# Testboard_Cables.net
KiCad netlist of a schematic drawn in EAGLE
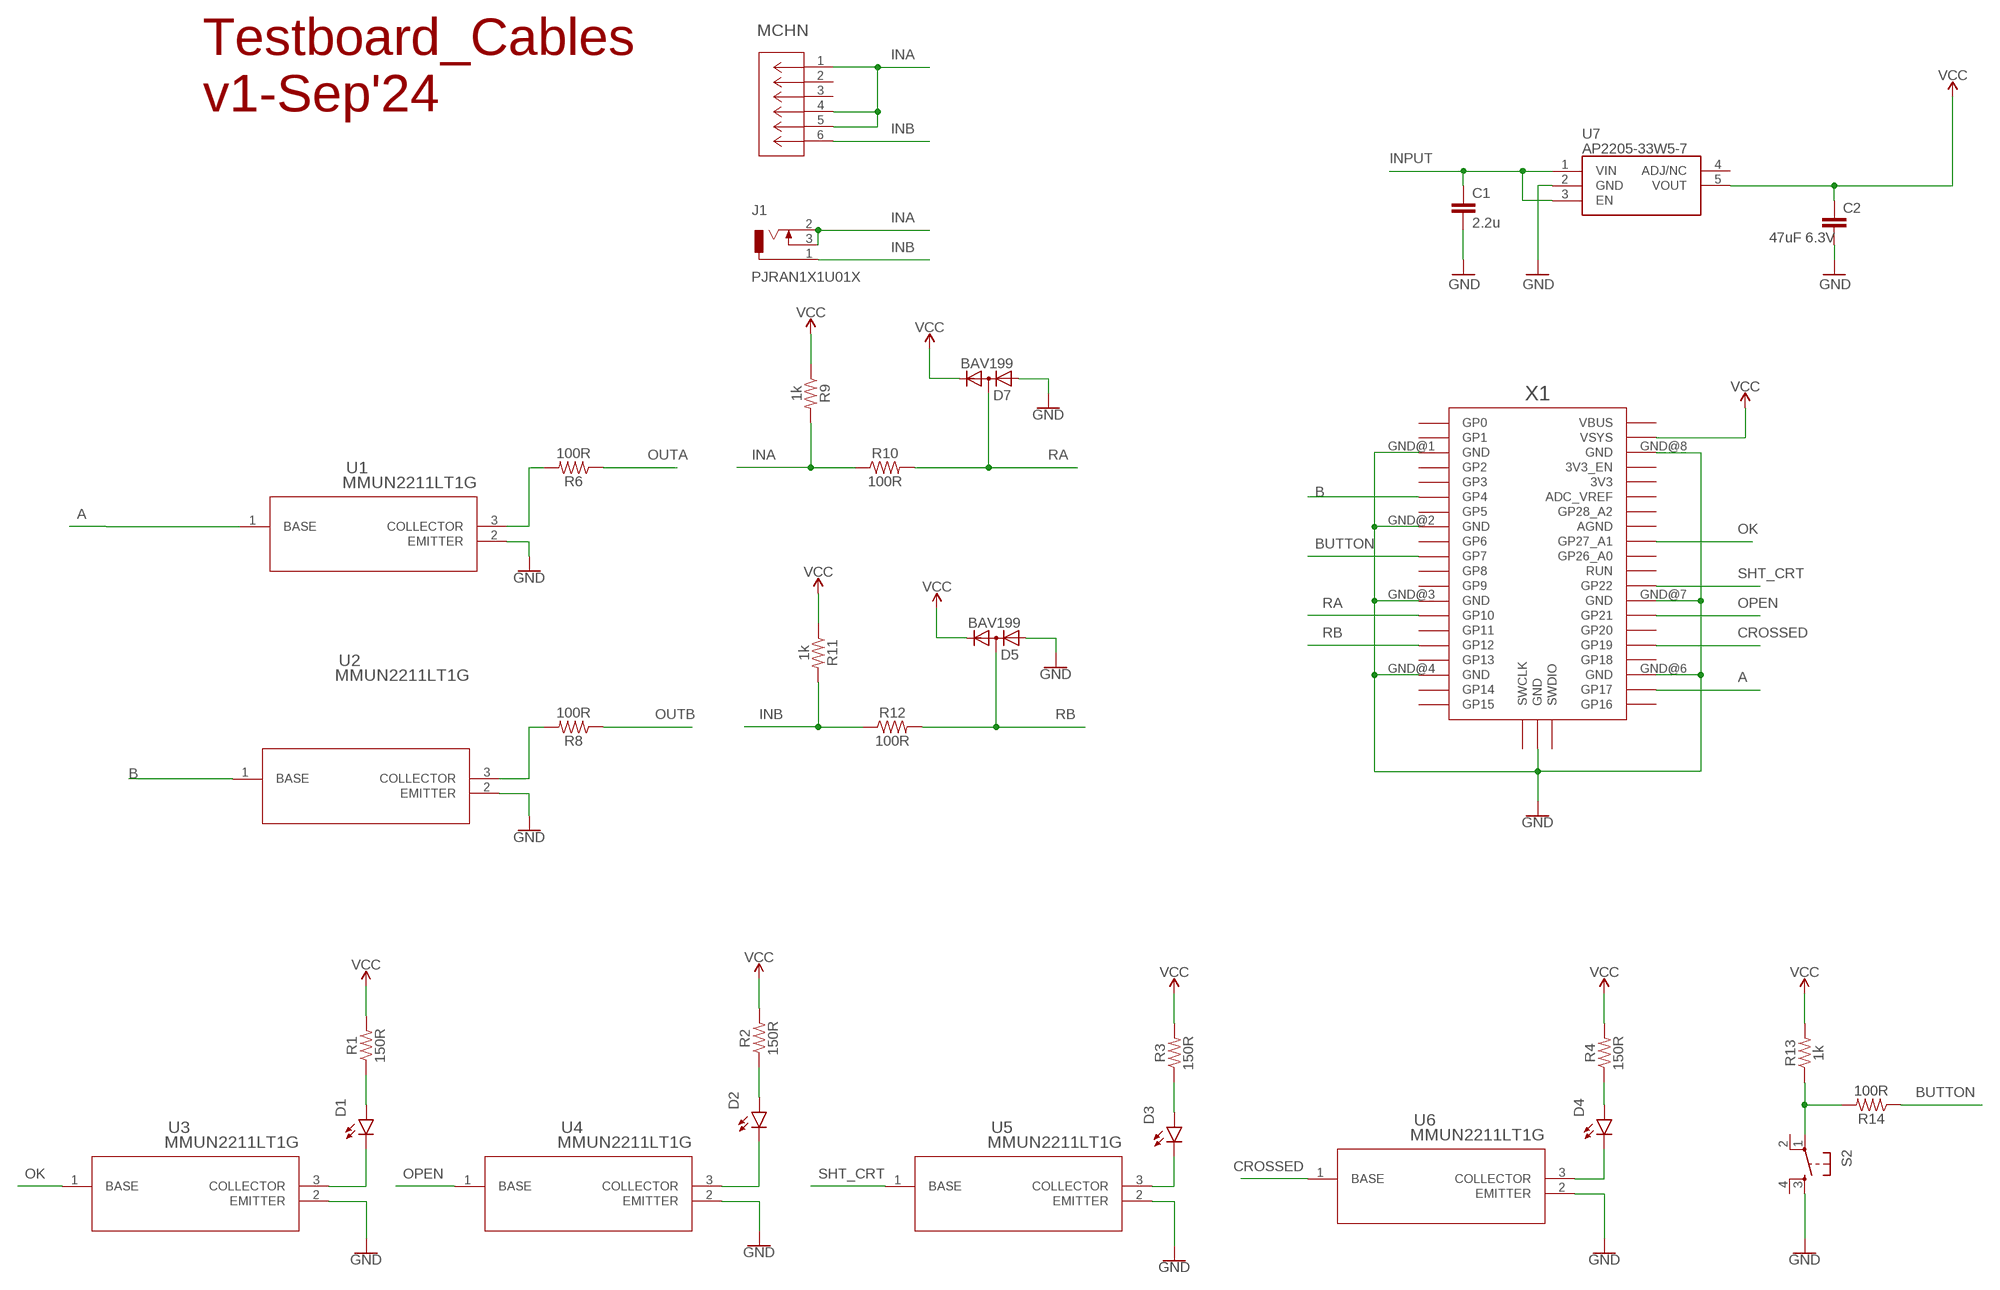
[diagram p0: schematic, sheet 1]

(export (version "E")
  (design (tool "Eeschema 10.0.6"))
  (components
    (comp (ref "C1")
      (value "2.2u")
      (footprint "eagle-import:0603-CAP")
      (libsource (lib "eagle-import") (part "4.7UF-6.3V-10%(0603)0603"))
    )
    (comp (ref "C2")
      (value "47uF 6.3V")
      (footprint "eagle-import:0603-CAP")
      (libsource (lib "eagle-import") (part "4.7UF-6.3V-10%(0603)0603"))
    )
    (comp (ref "D1")
      (value "LED3MM")
      (footprint "eagle-import:LED_3MM")
      (libsource (lib "eagle-import") (part "LED3MM"))
    )
    (comp (ref "D2")
      (value "LED3MM")
      (footprint "eagle-import:LED_3MM")
      (libsource (lib "eagle-import") (part "LED3MM"))
    )
    (comp (ref "D3")
      (value "LED3MM")
      (footprint "eagle-import:LED_3MM")
      (libsource (lib "eagle-import") (part "LED3MM"))
    )
    (comp (ref "D4")
      (value "LED3MM")
      (footprint "eagle-import:LED_3MM")
      (libsource (lib "eagle-import") (part "LED3MM"))
    )
    (comp (ref "D5")
      (value "BAV199")
      (footprint "eagle-import:SOT23")
      (libsource (lib "eagle-import") (part "BAV199"))
    )
    (comp (ref "D7")
      (value "BAV199")
      (footprint "eagle-import:SOT23")
      (libsource (lib "eagle-import") (part "BAV199"))
    )
    (comp (ref "J1")
      (value "PJRAN1X1U01X")
      (footprint "eagle-import:PJRAN1X1U01X")
      (fields
        (field (name "DIGIKEY_PART_NUMBER") "PJRAN1X1U01X-ND")
        (field (name "MANUFACTURER") "Switchcraft Inc.")
        (field (name "CREATED_BY") "PCBLayout.com")
      )
      (libsource (lib "eagle-import") (part "PJRAN1X1U01X"))
    )
    (comp (ref "MCHN")
      (value "ACJS-MHDR")
      (footprint "eagle-import:CONN_MHDR_AMP")
      (fields (field (name "COPYRIGHT") "Copyright (C) 2018 Accelerated Designs. All rights reserved"))
      (libsource (lib "eagle-import") (part "ACJS-MHDR"))
    )
    (comp (ref "R1")
      (value "150R")
      (footprint "eagle-import:1206")
      (libsource (lib "eagle-import") (part "RESISTOR1206"))
    )
    (comp (ref "R2")
      (value "150R")
      (footprint "eagle-import:1206")
      (libsource (lib "eagle-import") (part "RESISTOR1206"))
    )
    (comp (ref "R3")
      (value "150R")
      (footprint "eagle-import:1206")
      (libsource (lib "eagle-import") (part "RESISTOR1206"))
    )
    (comp (ref "R4")
      (value "150R")
      (footprint "eagle-import:1206")
      (libsource (lib "eagle-import") (part "RESISTOR1206"))
    )
    (comp (ref "R6")
      (value "100R")
      (footprint "eagle-import:1206")
      (libsource (lib "eagle-import") (part "RESISTOR1206"))
    )
    (comp (ref "R8")
      (value "100R")
      (footprint "eagle-import:1206")
      (libsource (lib "eagle-import") (part "RESISTOR1206"))
    )
    (comp (ref "R9")
      (value "1k")
      (footprint "eagle-import:1206")
      (libsource (lib "eagle-import") (part "RESISTOR1206"))
    )
    (comp (ref "R10")
      (value "100R")
      (footprint "eagle-import:1206")
      (libsource (lib "eagle-import") (part "RESISTOR1206"))
    )
    (comp (ref "R11")
      (value "1k")
      (footprint "eagle-import:1206")
      (libsource (lib "eagle-import") (part "RESISTOR1206"))
    )
    (comp (ref "R12")
      (value "100R")
      (footprint "eagle-import:1206")
      (libsource (lib "eagle-import") (part "RESISTOR1206"))
    )
    (comp (ref "R13")
      (value "1k")
      (footprint "eagle-import:1206")
      (libsource (lib "eagle-import") (part "RESISTOR1206"))
    )
    (comp (ref "R14")
      (value "100R")
      (footprint "eagle-import:1206")
      (libsource (lib "eagle-import") (part "RESISTOR1206"))
    )
    (comp (ref "S2")
      (value "TAC_SWITCH_KSC931G-SMD")
      (footprint "eagle-import:TAC_SW_SMD_KSC931G")
      (libsource (lib "eagle-import") (part "TAC_SWITCH_KSC931G-SMD"))
    )
    (comp (ref "U1")
      (value "MMUN2211LT1G")
      (footprint "eagle-import:SOT-23-3_1P4X3P040_ONS")
      (fields (field (name "COPYRIGHT") "Copyright (C) 2024 Ultra Librarian. All rights reserved."))
      (libsource (lib "eagle-import") (part "MMUN2211LT1G"))
    )
    (comp (ref "U2")
      (value "MMUN2211LT1G")
      (footprint "eagle-import:SOT-23-3_1P4X3P040_ONS")
      (fields (field (name "COPYRIGHT") "Copyright (C) 2024 Ultra Librarian. All rights reserved."))
      (libsource (lib "eagle-import") (part "MMUN2211LT1G"))
    )
    (comp (ref "U3")
      (value "MMUN2211LT1G")
      (footprint "eagle-import:SOT-23-3_1P4X3P040_ONS")
      (fields (field (name "COPYRIGHT") "Copyright (C) 2024 Ultra Librarian. All rights reserved."))
      (libsource (lib "eagle-import") (part "MMUN2211LT1G"))
    )
    (comp (ref "U4")
      (value "MMUN2211LT1G")
      (footprint "eagle-import:SOT-23-3_1P4X3P040_ONS")
      (fields (field (name "COPYRIGHT") "Copyright (C) 2024 Ultra Librarian. All rights reserved."))
      (libsource (lib "eagle-import") (part "MMUN2211LT1G"))
    )
    (comp (ref "U5")
      (value "MMUN2211LT1G")
      (footprint "eagle-import:SOT-23-3_1P4X3P040_ONS")
      (fields (field (name "COPYRIGHT") "Copyright (C) 2024 Ultra Librarian. All rights reserved."))
      (libsource (lib "eagle-import") (part "MMUN2211LT1G"))
    )
    (comp (ref "U6")
      (value "MMUN2211LT1G")
      (footprint "eagle-import:SOT-23-3_1P4X3P040_ONS")
      (fields (field (name "COPYRIGHT") "Copyright (C) 2024 Ultra Librarian. All rights reserved."))
      (libsource (lib "eagle-import") (part "MMUN2211LT1G"))
    )
    (comp (ref "U7")
      (value "AP2205-33W5-7")
      (footprint "eagle-import:SOT95P282X145-5N")
      (fields
        (field (name "MANUFACTURER_PART_NUMBER") "AP2205-W5-7")
        (field (name "MOUSER_PART_NUMBER") "621-AP2205-W5-7")
      )
      (libsource (lib "eagle-import") (part "AP2205-W5-7"))
    )
    (comp (ref "X1")
      (value "RPI_PICO_IG-TH")
      (footprint "eagle-import:RPI_PICO_TH")
      (libsource (lib "eagle-import") (part "RPI_PICO_IG-TH"))
    )
  )
  (nets
    (net (code "1") (name "/A") (class "Default")
      (node (ref "U1") (pin "1") (pinfunction "BASE_1") (pintype "passive"))
      (node (ref "X1") (pin "GP17") (pinfunction "GP17_GP17") (pintype "bidirectional"))
    )
    (net (code "2") (name "/B") (class "Default")
      (node (ref "U2") (pin "1") (pinfunction "BASE_1") (pintype "passive"))
      (node (ref "X1") (pin "GP4") (pinfunction "GP4_GP4") (pintype "bidirectional"))
    )
    (net (code "3") (name "/BUTTON") (class "Default")
      (node (ref "R14") (pin "1") (pinfunction "1_1") (pintype "passive"))
      (node (ref "X1") (pin "GP7") (pinfunction "GP7_GP7") (pintype "bidirectional"))
    )
    (net (code "4") (name "/CROSSED") (class "Default")
      (node (ref "U6") (pin "1") (pinfunction "BASE_1") (pintype "passive"))
      (node (ref "X1") (pin "GP19") (pinfunction "GP19_GP19") (pintype "bidirectional"))
    )
    (net (code "5") (name "/INA") (class "Default")
      (node (ref "J1") (pin "2") (pinfunction "2_2") (pintype "passive"))
      (node (ref "J1") (pin "3") (pinfunction "3_3") (pintype "passive"))
      (node (ref "MCHN") (pin "1") (pinfunction "1_1") (pintype "passive"))
      (node (ref "MCHN") (pin "4") (pinfunction "4_4") (pintype "passive"))
      (node (ref "MCHN") (pin "5") (pinfunction "5_5") (pintype "passive"))
      (node (ref "R10") (pin "1") (pinfunction "1_1") (pintype "passive"))
      (node (ref "R9") (pin "2") (pinfunction "2_2") (pintype "passive"))
    )
    (net (code "6") (name "/INB") (class "Default")
      (node (ref "J1") (pin "1") (pinfunction "1_1") (pintype "passive"))
      (node (ref "MCHN") (pin "6") (pinfunction "6_6") (pintype "passive"))
      (node (ref "R11") (pin "2") (pinfunction "2_2") (pintype "passive"))
      (node (ref "R12") (pin "1") (pinfunction "1_1") (pintype "passive"))
    )
    (net (code "7") (name "/INPUT") (class "Default")
      (node (ref "C1") (pin "1") (pinfunction "1_1") (pintype "passive"))
      (node (ref "U7") (pin "1") (pinfunction "VIN_1") (pintype "bidirectional"))
      (node (ref "U7") (pin "3") (pinfunction "EN_3") (pintype "bidirectional"))
    )
    (net (code "8") (name "/OK") (class "Default")
      (node (ref "U3") (pin "1") (pinfunction "BASE_1") (pintype "passive"))
      (node (ref "X1") (pin "GP27_A1") (pinfunction "GP27_A1_GP27_A1") (pintype "bidirectional"))
    )
    (net (code "9") (name "/OPEN") (class "Default")
      (node (ref "U4") (pin "1") (pinfunction "BASE_1") (pintype "passive"))
      (node (ref "X1") (pin "GP21") (pinfunction "GP21_GP21") (pintype "bidirectional"))
    )
    (net (code "10") (name "/OUTA") (class "Default")
      (node (ref "R6") (pin "1") (pinfunction "1_1") (pintype "passive"))
    )
    (net (code "11") (name "/OUTB") (class "Default")
      (node (ref "R8") (pin "1") (pinfunction "1_1") (pintype "passive"))
    )
    (net (code "12") (name "/RA") (class "Default")
      (node (ref "D7") (pin "3") (pinfunction "AC_3") (pintype "passive"))
      (node (ref "R10") (pin "2") (pinfunction "2_2") (pintype "passive"))
      (node (ref "X1") (pin "GP10") (pinfunction "GP10_GP10") (pintype "bidirectional"))
    )
    (net (code "13") (name "/RB") (class "Default")
      (node (ref "D5") (pin "3") (pinfunction "AC_3") (pintype "passive"))
      (node (ref "R12") (pin "2") (pinfunction "2_2") (pintype "passive"))
      (node (ref "X1") (pin "GP12") (pinfunction "GP12_GP12") (pintype "bidirectional"))
    )
    (net (code "14") (name "/SHT_CRT") (class "Default")
      (node (ref "U5") (pin "1") (pinfunction "BASE_1") (pintype "passive"))
      (node (ref "X1") (pin "GP22") (pinfunction "GP22_GP22") (pintype "bidirectional"))
    )
    (net (code "15") (name "GND") (class "Default")
      (node (ref "C1") (pin "2") (pinfunction "2_2") (pintype "passive"))
      (node (ref "C2") (pin "2") (pinfunction "2_2") (pintype "passive"))
      (node (ref "D5") (pin "1") (pinfunction "A_1") (pintype "passive"))
      (node (ref "D7") (pin "1") (pinfunction "A_1") (pintype "passive"))
      (node (ref "S2") (pin "3") (pinfunction "3_3") (pintype "passive"))
      (node (ref "U1") (pin "2") (pinfunction "EMITTER_2") (pintype "passive"))
      (node (ref "U2") (pin "2") (pinfunction "EMITTER_2") (pintype "passive"))
      (node (ref "U3") (pin "2") (pinfunction "EMITTER_2") (pintype "passive"))
      (node (ref "U4") (pin "2") (pinfunction "EMITTER_2") (pintype "passive"))
      (node (ref "U5") (pin "2") (pinfunction "EMITTER_2") (pintype "passive"))
      (node (ref "U6") (pin "2") (pinfunction "EMITTER_2") (pintype "passive"))
      (node (ref "U7") (pin "2") (pinfunction "GND_2") (pintype "bidirectional"))
      (node (ref "X1") (pin "GND@1") (pinfunction "GND_GND@1") (pintype "bidirectional"))
      (node (ref "X1") (pin "GND@2") (pinfunction "GND_GND@2") (pintype "bidirectional"))
      (node (ref "X1") (pin "GND@3") (pinfunction "GND_GND@3") (pintype "bidirectional"))
      (node (ref "X1") (pin "GND@4") (pinfunction "GND_GND@4") (pintype "bidirectional"))
      (node (ref "X1") (pin "GND@5") (pinfunction "GND_GND@5") (pintype "bidirectional"))
      (node (ref "X1") (pin "GND@6") (pinfunction "GND_GND@6") (pintype "bidirectional"))
      (node (ref "X1") (pin "GND@7") (pinfunction "GND_GND@7") (pintype "bidirectional"))
      (node (ref "X1") (pin "GND@8") (pinfunction "GND_GND@8") (pintype "bidirectional"))
    )
    (net (code "16") (name "Net-(D1-C)") (class "Default")
      (node (ref "D1") (pin "K") (pinfunction "C_K") (pintype "passive"))
      (node (ref "U3") (pin "3") (pinfunction "COLLECTOR_3") (pintype "passive"))
    )
    (net (code "17") (name "Net-(D1-PadA)") (class "Default")
      (node (ref "D1") (pin "A") (pinfunction "A_A") (pintype "passive"))
      (node (ref "R1") (pin "1") (pinfunction "1_1") (pintype "passive"))
    )
    (net (code "18") (name "Net-(D2-C)") (class "Default")
      (node (ref "D2") (pin "K") (pinfunction "C_K") (pintype "passive"))
      (node (ref "U4") (pin "3") (pinfunction "COLLECTOR_3") (pintype "passive"))
    )
    (net (code "19") (name "Net-(D2-PadA)") (class "Default")
      (node (ref "D2") (pin "A") (pinfunction "A_A") (pintype "passive"))
      (node (ref "R2") (pin "1") (pinfunction "1_1") (pintype "passive"))
    )
    (net (code "20") (name "Net-(D3-C)") (class "Default")
      (node (ref "D3") (pin "K") (pinfunction "C_K") (pintype "passive"))
      (node (ref "U5") (pin "3") (pinfunction "COLLECTOR_3") (pintype "passive"))
    )
    (net (code "21") (name "Net-(D3-PadA)") (class "Default")
      (node (ref "D3") (pin "A") (pinfunction "A_A") (pintype "passive"))
      (node (ref "R3") (pin "1") (pinfunction "1_1") (pintype "passive"))
    )
    (net (code "22") (name "Net-(D4-C)") (class "Default")
      (node (ref "D4") (pin "K") (pinfunction "C_K") (pintype "passive"))
      (node (ref "U6") (pin "3") (pinfunction "COLLECTOR_3") (pintype "passive"))
    )
    (net (code "23") (name "Net-(D4-PadA)") (class "Default")
      (node (ref "D4") (pin "A") (pinfunction "A_A") (pintype "passive"))
      (node (ref "R4") (pin "1") (pinfunction "1_1") (pintype "passive"))
    )
    (net (code "24") (name "Net-(R13-Pad1)") (class "Default")
      (node (ref "R13") (pin "1") (pinfunction "1_1") (pintype "passive"))
      (node (ref "R14") (pin "2") (pinfunction "2_2") (pintype "passive"))
      (node (ref "S2") (pin "1") (pinfunction "1_1") (pintype "passive"))
    )
    (net (code "25") (name "Net-(U1-COLLECTOR)") (class "Default")
      (node (ref "R6") (pin "2") (pinfunction "2_2") (pintype "passive"))
      (node (ref "U1") (pin "3") (pinfunction "COLLECTOR_3") (pintype "passive"))
    )
    (net (code "26") (name "Net-(U2-COLLECTOR)") (class "Default")
      (node (ref "R8") (pin "2") (pinfunction "2_2") (pintype "passive"))
      (node (ref "U2") (pin "3") (pinfunction "COLLECTOR_3") (pintype "passive"))
    )
    (net (code "27") (name "VCC") (class "Default")
      (node (ref "C2") (pin "1") (pinfunction "1_1") (pintype "passive"))
      (node (ref "D5") (pin "2") (pinfunction "C_2") (pintype "passive"))
      (node (ref "D7") (pin "2") (pinfunction "C_2") (pintype "passive"))
      (node (ref "R1") (pin "2") (pinfunction "2_2") (pintype "passive"))
      (node (ref "R11") (pin "1") (pinfunction "1_1") (pintype "passive"))
      (node (ref "R13") (pin "2") (pinfunction "2_2") (pintype "passive"))
      (node (ref "R2") (pin "2") (pinfunction "2_2") (pintype "passive"))
      (node (ref "R3") (pin "2") (pinfunction "2_2") (pintype "passive"))
      (node (ref "R4") (pin "2") (pinfunction "2_2") (pintype "passive"))
      (node (ref "R9") (pin "1") (pinfunction "1_1") (pintype "passive"))
      (node (ref "U7") (pin "5") (pinfunction "VOUT_5") (pintype "bidirectional"))
      (node (ref "X1") (pin "VSYS") (pinfunction "VSYS_VSYS") (pintype "bidirectional"))
    )
    (net (code "28") (name "unconnected-(MCHN-Pad2)") (class "Default")
      (node (ref "MCHN") (pin "2") (pinfunction "2_2") (pintype "passive"))
    )
    (net (code "29") (name "unconnected-(MCHN-Pad3)") (class "Default")
      (node (ref "MCHN") (pin "3") (pinfunction "3_3") (pintype "passive"))
    )
    (net (code "30") (name "unconnected-(S2-Pad2)") (class "Default")
      (node (ref "S2") (pin "2") (pinfunction "2_2") (pintype "passive"))
    )
    (net (code "31") (name "unconnected-(S2-Pad4)") (class "Default")
      (node (ref "S2") (pin "4") (pinfunction "4_4") (pintype "passive"))
    )
    (net (code "32") (name "unconnected-(U7-ADJ{slash}NC-Pad4)") (class "Default")
      (node (ref "U7") (pin "4") (pinfunction "ADJ/NC_4") (pintype "bidirectional"))
    )
    (net (code "33") (name "unconnected-(X1-Pad3V3)") (class "Default")
      (node (ref "X1") (pin "3V3") (pinfunction "3V3_3V3") (pintype "bidirectional"))
    )
    (net (code "34") (name "unconnected-(X1-Pad3V3_EN)") (class "Default")
      (node (ref "X1") (pin "3V3_EN") (pinfunction "3V3_EN_3V3_EN") (pintype "bidirectional"))
    )
    (net (code "35") (name "unconnected-(X1-PadADC_VREF)") (class "Default")
      (node (ref "X1") (pin "ADC_VREF") (pinfunction "ADC_VREF_ADC_VREF") (pintype "bidirectional"))
    )
    (net (code "36") (name "unconnected-(X1-PadAGND)") (class "Default")
      (node (ref "X1") (pin "AGND") (pinfunction "AGND_AGND") (pintype "bidirectional"))
    )
    (net (code "37") (name "unconnected-(X1-PadGP0)") (class "Default")
      (node (ref "X1") (pin "GP0") (pinfunction "GP0_GP0") (pintype "bidirectional"))
    )
    (net (code "38") (name "unconnected-(X1-PadGP1)") (class "Default")
      (node (ref "X1") (pin "GP1") (pinfunction "GP1_GP1") (pintype "bidirectional"))
    )
    (net (code "39") (name "unconnected-(X1-PadGP2)") (class "Default")
      (node (ref "X1") (pin "GP2") (pinfunction "GP2_GP2") (pintype "bidirectional"))
    )
    (net (code "40") (name "unconnected-(X1-PadGP3)") (class "Default")
      (node (ref "X1") (pin "GP3") (pinfunction "GP3_GP3") (pintype "bidirectional"))
    )
    (net (code "41") (name "unconnected-(X1-PadGP5)") (class "Default")
      (node (ref "X1") (pin "GP5") (pinfunction "GP5_GP5") (pintype "bidirectional"))
    )
    (net (code "42") (name "unconnected-(X1-PadGP6)") (class "Default")
      (node (ref "X1") (pin "GP6") (pinfunction "GP6_GP6") (pintype "bidirectional"))
    )
    (net (code "43") (name "unconnected-(X1-PadGP8)") (class "Default")
      (node (ref "X1") (pin "GP8") (pinfunction "GP8_GP8") (pintype "bidirectional"))
    )
    (net (code "44") (name "unconnected-(X1-PadGP9)") (class "Default")
      (node (ref "X1") (pin "GP9") (pinfunction "GP9_GP9") (pintype "bidirectional"))
    )
    (net (code "45") (name "unconnected-(X1-PadGP11)") (class "Default")
      (node (ref "X1") (pin "GP11") (pinfunction "GP11_GP11") (pintype "bidirectional"))
    )
    (net (code "46") (name "unconnected-(X1-PadGP13)") (class "Default")
      (node (ref "X1") (pin "GP13") (pinfunction "GP13_GP13") (pintype "bidirectional"))
    )
    (net (code "47") (name "unconnected-(X1-PadGP14)") (class "Default")
      (node (ref "X1") (pin "GP14") (pinfunction "GP14_GP14") (pintype "bidirectional"))
    )
    (net (code "48") (name "unconnected-(X1-PadGP15)") (class "Default")
      (node (ref "X1") (pin "GP15") (pinfunction "GP15_GP15") (pintype "bidirectional"))
    )
    (net (code "49") (name "unconnected-(X1-PadGP16)") (class "Default")
      (node (ref "X1") (pin "GP16") (pinfunction "GP16_GP16") (pintype "bidirectional"))
    )
    (net (code "50") (name "unconnected-(X1-PadGP18)") (class "Default")
      (node (ref "X1") (pin "GP18") (pinfunction "GP18_GP18") (pintype "bidirectional"))
    )
    (net (code "51") (name "unconnected-(X1-PadGP20)") (class "Default")
      (node (ref "X1") (pin "GP20") (pinfunction "GP20_GP20") (pintype "bidirectional"))
    )
    (net (code "52") (name "unconnected-(X1-PadGP26_A0)") (class "Default")
      (node (ref "X1") (pin "GP26_A0") (pinfunction "GP26_A0_GP26_A0") (pintype "bidirectional"))
    )
    (net (code "53") (name "unconnected-(X1-PadGP28_A2)") (class "Default")
      (node (ref "X1") (pin "GP28_A2") (pinfunction "GP28_A2_GP28_A2") (pintype "bidirectional"))
    )
    (net (code "54") (name "unconnected-(X1-PadRUN)") (class "Default")
      (node (ref "X1") (pin "RUN") (pinfunction "RUN_RUN") (pintype "bidirectional"))
    )
    (net (code "55") (name "unconnected-(X1-PadSWCLK)") (class "Default")
      (node (ref "X1") (pin "SWCLK") (pinfunction "SWCLK_SWCLK") (pintype "bidirectional"))
    )
    (net (code "56") (name "unconnected-(X1-PadSWDIO)") (class "Default")
      (node (ref "X1") (pin "SWDIO") (pinfunction "SWDIO_SWDIO") (pintype "bidirectional"))
    )
    (net (code "57") (name "unconnected-(X1-PadVBUS)") (class "Default")
      (node (ref "X1") (pin "VBUS") (pinfunction "VBUS_VBUS") (pintype "bidirectional"))
    )
  )
)
